# ict_v361-xs-boost.net
KiCad netlist of a schematic drawn in EAGLE
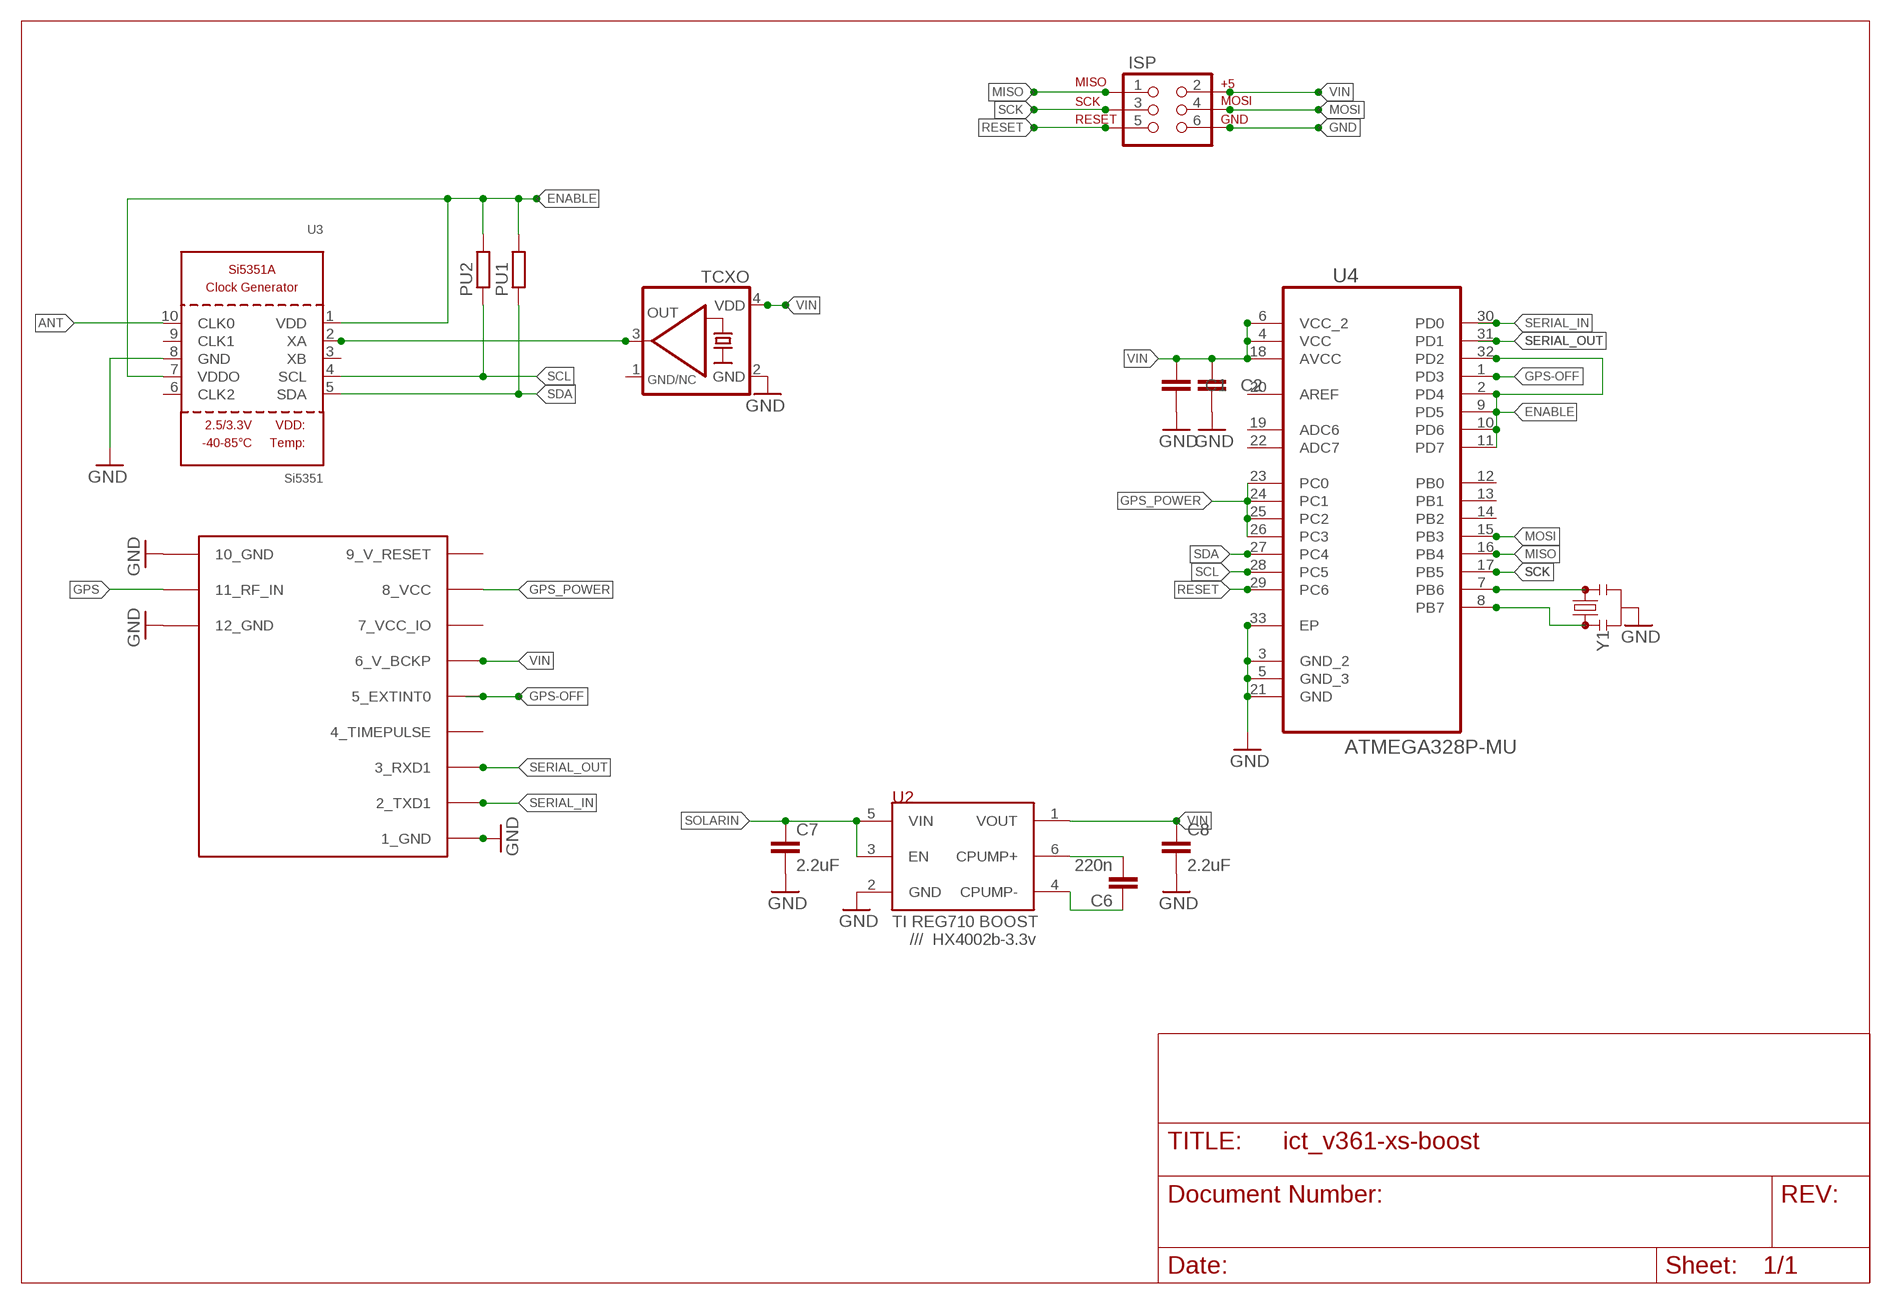
[diagram p0: schematic, sheet 1]

(export (version "E")
  (design (tool "Eeschema 10.0.6"))
  (components
    (comp (ref "C1")
      (value "C-EUC0603K")
      (footprint "eagle-import:C0603K")
      (libsource (lib "eagle-import") (part "C-EUC0603K"))
    )
    (comp (ref "C2")
      (value "C-EUC0603K")
      (footprint "eagle-import:C0603K")
      (libsource (lib "eagle-import") (part "C-EUC0603K"))
    )
    (comp (ref "C6")
      (value "220n")
      (footprint "eagle-import:0603-CAP")
      (libsource (lib "eagle-import") (part "CAP0603-CAP"))
    )
    (comp (ref "C7")
      (value "2.2uF")
      (footprint "eagle-import:0603-CAP")
      (libsource (lib "eagle-import") (part "CAP0603-CAP"))
    )
    (comp (ref "C8")
      (value "2.2uF")
      (footprint "eagle-import:0603-CAP")
      (libsource (lib "eagle-import") (part "CAP0603-CAP"))
    )
    (comp (ref "ISP")
      (value "AVR_SPI_PRG_6PTH")
      (footprint "eagle-import:2X3")
      (libsource (lib "eagle-import") (part "AVR_SPI_PRG_6PTH"))
    )
    (comp (ref "PU1")
      (value "R-EU_R0603")
      (footprint "eagle-import:R0603")
      (libsource (lib "eagle-import") (part "R-EU_R0603"))
    )
    (comp (ref "PU2")
      (value "R-EU_R0603")
      (footprint "eagle-import:R0603")
      (libsource (lib "eagle-import") (part "R-EU_R0603"))
    )
    (comp (ref "TCXO")
      (value "KXO-TCXO-CMOS-84")
      (footprint "eagle-import:3.2X2.5_KXO-84-TCXO")
      (libsource (lib "eagle-import") (part "KXO-TCXO-CMOS-84"))
    )
    (comp (ref "U$2")
      (value "UBLOX_MAX")
      (footprint "eagle-import:UBLOX_MAX")
      (libsource (lib "eagle-import") (part "UBLOX_MAX"))
    )
    (comp (ref "U2")
      (value "/// HX4002b-3.3v")
      (footprint "eagle-import:SOT-23-6L")
      (libsource (lib "eagle-import") (part "TI-REG710"))
    )
    (comp (ref "U3")
      (value "Si5351")
      (footprint "eagle-import:MSOP10")
      (libsource (lib "eagle-import") (part "SI5351A"))
    )
    (comp (ref "U4")
      (value "ATMEGA328P-MU")
      (footprint "eagle-import:QFN50P500X500X100-33N")
      (libsource (lib "eagle-import") (part "ATMEGA328P-MU"))
    )
    (comp (ref "Y1")
      (value "RESONATORSMD-4.5X2.0")
      (footprint "eagle-import:RESONATOR-SMD-4.5X2.0")
      (libsource (lib "eagle-import") (part "RESONATORSMD-4.5X2.0"))
    )
  )
  (nets
    (net (code "1") (name "/7_VCC_IO") (class "Default")
      (node (ref "U$2") (pin "7_VCC_IO") (pinfunction "7_VCC_IO_7_VCC_IO") (pintype "power_in"))
    )
    (net (code "2") (name "/9_V_RESET") (class "Default")
      (node (ref "U$2") (pin "9_V_RESET") (pinfunction "9_V_RESET_9_V_RESET") (pintype "power_in"))
    )
    (net (code "3") (name "/GND{slash}NC") (class "Default")
      (node (ref "TCXO") (pin "1") (pinfunction "GND/NC_1") (pintype "power_in"))
    )
    (net (code "4") (name "ANT") (class "Default")
      (node (ref "U3") (pin "10") (pinfunction "CLK0_10") (pintype "output"))
    )
    (net (code "5") (name "ENABLE") (class "Default")
      (node (ref "PU1") (pin "2") (pinfunction "2_2") (pintype "passive"))
      (node (ref "PU2") (pin "2") (pinfunction "2_2") (pintype "passive"))
      (node (ref "U3") (pin "1") (pinfunction "VDD_1") (pintype "power_in"))
      (node (ref "U3") (pin "7") (pinfunction "VDDO_7") (pintype "power_in"))
      (node (ref "U4") (pin "10") (pinfunction "PD6_10") (pintype "bidirectional"))
      (node (ref "U4") (pin "11") (pinfunction "PD7_11") (pintype "bidirectional"))
      (node (ref "U4") (pin "2") (pinfunction "PD4_2") (pintype "bidirectional"))
      (node (ref "U4") (pin "32") (pinfunction "PD2_32") (pintype "bidirectional"))
      (node (ref "U4") (pin "9") (pinfunction "PD5_9") (pintype "bidirectional"))
    )
    (net (code "6") (name "GND") (class "Default")
      (node (ref "C1") (pin "2") (pinfunction "2_2") (pintype "passive"))
      (node (ref "C2") (pin "2") (pinfunction "2_2") (pintype "passive"))
      (node (ref "C7") (pin "2") (pinfunction "2_2") (pintype "passive"))
      (node (ref "C8") (pin "2") (pinfunction "2_2") (pintype "passive"))
      (node (ref "ISP") (pin "6") (pinfunction "6_6") (pintype "passive"))
      (node (ref "TCXO") (pin "2") (pinfunction "GND_2") (pintype "power_in"))
      (node (ref "U$2") (pin "10_GND") (pinfunction "10_GND_10_GND") (pintype "power_in"))
      (node (ref "U$2") (pin "12_GND") (pinfunction "12_GND_12_GND") (pintype "power_in"))
      (node (ref "U$2") (pin "1_GND") (pinfunction "1_GND_1_GND") (pintype "power_in"))
      (node (ref "U2") (pin "2") (pinfunction "GND_2") (pintype "bidirectional"))
      (node (ref "U3") (pin "8") (pinfunction "GND_8") (pintype "power_in"))
      (node (ref "U4") (pin "21") (pinfunction "GND_21") (pintype "passive"))
      (node (ref "U4") (pin "3") (pinfunction "GND_2_3") (pintype "passive"))
      (node (ref "U4") (pin "33") (pinfunction "EP_33") (pintype "passive"))
      (node (ref "U4") (pin "5") (pinfunction "GND_3_5") (pintype "passive"))
      (node (ref "Y1") (pin "2") (pinfunction "2_2") (pintype "passive"))
    )
    (net (code "7") (name "GPS") (class "Default")
      (node (ref "U$2") (pin "11_RF_IN") (pinfunction "11_RF_IN_11_RF_IN") (pintype "bidirectional"))
    )
    (net (code "8") (name "GPS-OFF") (class "Default")
      (node (ref "U$2") (pin "5_EXTINT0") (pinfunction "5_EXTINT0_5_EXTINT0") (pintype "bidirectional"))
      (node (ref "U4") (pin "1") (pinfunction "PD3_1") (pintype "bidirectional"))
    )
    (net (code "9") (name "GPS_POWER") (class "Default")
      (node (ref "U$2") (pin "8_VCC") (pinfunction "8_VCC_8_VCC") (pintype "power_in"))
      (node (ref "U4") (pin "23") (pinfunction "PC0_23") (pintype "bidirectional"))
      (node (ref "U4") (pin "24") (pinfunction "PC1_24") (pintype "bidirectional"))
      (node (ref "U4") (pin "25") (pinfunction "PC2_25") (pintype "bidirectional"))
      (node (ref "U4") (pin "26") (pinfunction "PC3_26") (pintype "bidirectional"))
    )
    (net (code "10") (name "MISO") (class "Default")
      (node (ref "ISP") (pin "1") (pinfunction "1_1") (pintype "passive"))
      (node (ref "U4") (pin "16") (pinfunction "PB4_16") (pintype "bidirectional"))
    )
    (net (code "11") (name "MOSI") (class "Default")
      (node (ref "ISP") (pin "4") (pinfunction "4_4") (pintype "passive"))
      (node (ref "U4") (pin "15") (pinfunction "PB3_15") (pintype "bidirectional"))
    )
    (net (code "12") (name "Net-(TCXO-OUT)") (class "Default")
      (node (ref "TCXO") (pin "3") (pinfunction "OUT_3") (pintype "output"))
      (node (ref "U3") (pin "2") (pinfunction "XA_2") (pintype "input"))
    )
    (net (code "13") (name "Net-(U2-CPUMP+)") (class "Default")
      (node (ref "C6") (pin "2") (pinfunction "2_2") (pintype "passive"))
      (node (ref "U2") (pin "6") (pinfunction "CPUMP+_6") (pintype "bidirectional"))
    )
    (net (code "14") (name "Net-(U2-CPUMP-)") (class "Default")
      (node (ref "C6") (pin "1") (pinfunction "1_1") (pintype "passive"))
      (node (ref "U2") (pin "4") (pinfunction "CPUMP-_4") (pintype "bidirectional"))
    )
    (net (code "15") (name "Net-(U4-PB6)") (class "Default")
      (node (ref "U4") (pin "7") (pinfunction "PB6_7") (pintype "bidirectional"))
      (node (ref "Y1") (pin "3") (pinfunction "3_3") (pintype "passive"))
    )
    (net (code "16") (name "Net-(U4-PB7)") (class "Default")
      (node (ref "U4") (pin "8") (pinfunction "PB7_8") (pintype "bidirectional"))
      (node (ref "Y1") (pin "1") (pinfunction "1_1") (pintype "passive"))
    )
    (net (code "17") (name "RESET") (class "Default")
      (node (ref "ISP") (pin "5") (pinfunction "5_5") (pintype "passive"))
      (node (ref "U4") (pin "29") (pinfunction "PC6_29") (pintype "bidirectional"))
    )
    (net (code "18") (name "SCK") (class "Default")
      (node (ref "ISP") (pin "3") (pinfunction "3_3") (pintype "passive"))
      (node (ref "U4") (pin "17") (pinfunction "PB5_17") (pintype "bidirectional"))
    )
    (net (code "19") (name "SCL") (class "Default")
      (node (ref "PU2") (pin "1") (pinfunction "1_1") (pintype "passive"))
      (node (ref "U3") (pin "4") (pinfunction "SCL_4") (pintype "input"))
      (node (ref "U4") (pin "28") (pinfunction "PC5_28") (pintype "bidirectional"))
    )
    (net (code "20") (name "SDA") (class "Default")
      (node (ref "PU1") (pin "1") (pinfunction "1_1") (pintype "passive"))
      (node (ref "U3") (pin "5") (pinfunction "SDA_5") (pintype "bidirectional"))
      (node (ref "U4") (pin "27") (pinfunction "PC4_27") (pintype "bidirectional"))
    )
    (net (code "21") (name "SERIAL_IN") (class "Default")
      (node (ref "U$2") (pin "2_TXD1") (pinfunction "2_TXD1_2_TXD1") (pintype "bidirectional"))
      (node (ref "U4") (pin "30") (pinfunction "PD0_30") (pintype "bidirectional"))
    )
    (net (code "22") (name "SERIAL_OUT") (class "Default")
      (node (ref "U$2") (pin "3_RXD1") (pinfunction "3_RXD1_3_RXD1") (pintype "bidirectional"))
      (node (ref "U4") (pin "31") (pinfunction "PD1_31") (pintype "bidirectional"))
    )
    (net (code "23") (name "SOLARIN") (class "Default")
      (node (ref "C7") (pin "1") (pinfunction "1_1") (pintype "passive"))
      (node (ref "U2") (pin "3") (pinfunction "EN_3") (pintype "bidirectional"))
      (node (ref "U2") (pin "5") (pinfunction "VIN_5") (pintype "bidirectional"))
    )
    (net (code "24") (name "VIN") (class "Default")
      (node (ref "C1") (pin "1") (pinfunction "1_1") (pintype "passive"))
      (node (ref "C2") (pin "1") (pinfunction "1_1") (pintype "passive"))
      (node (ref "C8") (pin "1") (pinfunction "1_1") (pintype "passive"))
      (node (ref "ISP") (pin "2") (pinfunction "2_2") (pintype "passive"))
      (node (ref "TCXO") (pin "4") (pinfunction "VDD_4") (pintype "power_in"))
      (node (ref "U$2") (pin "6_V_BCKP") (pinfunction "6_V_BCKP_6_V_BCKP") (pintype "bidirectional"))
      (node (ref "U2") (pin "1") (pinfunction "VOUT_1") (pintype "bidirectional"))
      (node (ref "U4") (pin "18") (pinfunction "AVCC_18") (pintype "power_in"))
      (node (ref "U4") (pin "4") (pinfunction "VCC_4") (pintype "power_in"))
      (node (ref "U4") (pin "6") (pinfunction "VCC_2_6") (pintype "power_in"))
    )
    (net (code "25") (name "unconnected-(U$2-Pad4_TIMEPULSE)") (class "Default")
      (node (ref "U$2") (pin "4_TIMEPULSE") (pinfunction "4_TIMEPULSE_4_TIMEPULSE") (pintype "bidirectional"))
    )
    (net (code "26") (name "unconnected-(U3-CLK1-Pad9)") (class "Default")
      (node (ref "U3") (pin "9") (pinfunction "CLK1_9") (pintype "output"))
    )
    (net (code "27") (name "unconnected-(U3-CLK2-Pad6)") (class "Default")
      (node (ref "U3") (pin "6") (pinfunction "CLK2_6") (pintype "output"))
    )
    (net (code "28") (name "unconnected-(U3-XB-Pad3)") (class "Default")
      (node (ref "U3") (pin "3") (pinfunction "XB_3") (pintype "input"))
    )
    (net (code "29") (name "unconnected-(U4-ADC6-Pad19)") (class "Default")
      (node (ref "U4") (pin "19") (pinfunction "ADC6_19") (pintype "input"))
    )
    (net (code "30") (name "unconnected-(U4-ADC7-Pad22)") (class "Default")
      (node (ref "U4") (pin "22") (pinfunction "ADC7_22") (pintype "input"))
    )
    (net (code "31") (name "unconnected-(U4-AREF-Pad20)") (class "Default")
      (node (ref "U4") (pin "20") (pinfunction "AREF_20") (pintype "input"))
    )
    (net (code "32") (name "unconnected-(U4-PB0-Pad12)") (class "Default")
      (node (ref "U4") (pin "12") (pinfunction "PB0_12") (pintype "bidirectional"))
    )
    (net (code "33") (name "unconnected-(U4-PB1-Pad13)") (class "Default")
      (node (ref "U4") (pin "13") (pinfunction "PB1_13") (pintype "bidirectional"))
    )
    (net (code "34") (name "unconnected-(U4-PB2-Pad14)") (class "Default")
      (node (ref "U4") (pin "14") (pinfunction "PB2_14") (pintype "bidirectional"))
    )
  )
)
